# NESCAT.net
KiCad netlist of a schematic drawn in EAGLE
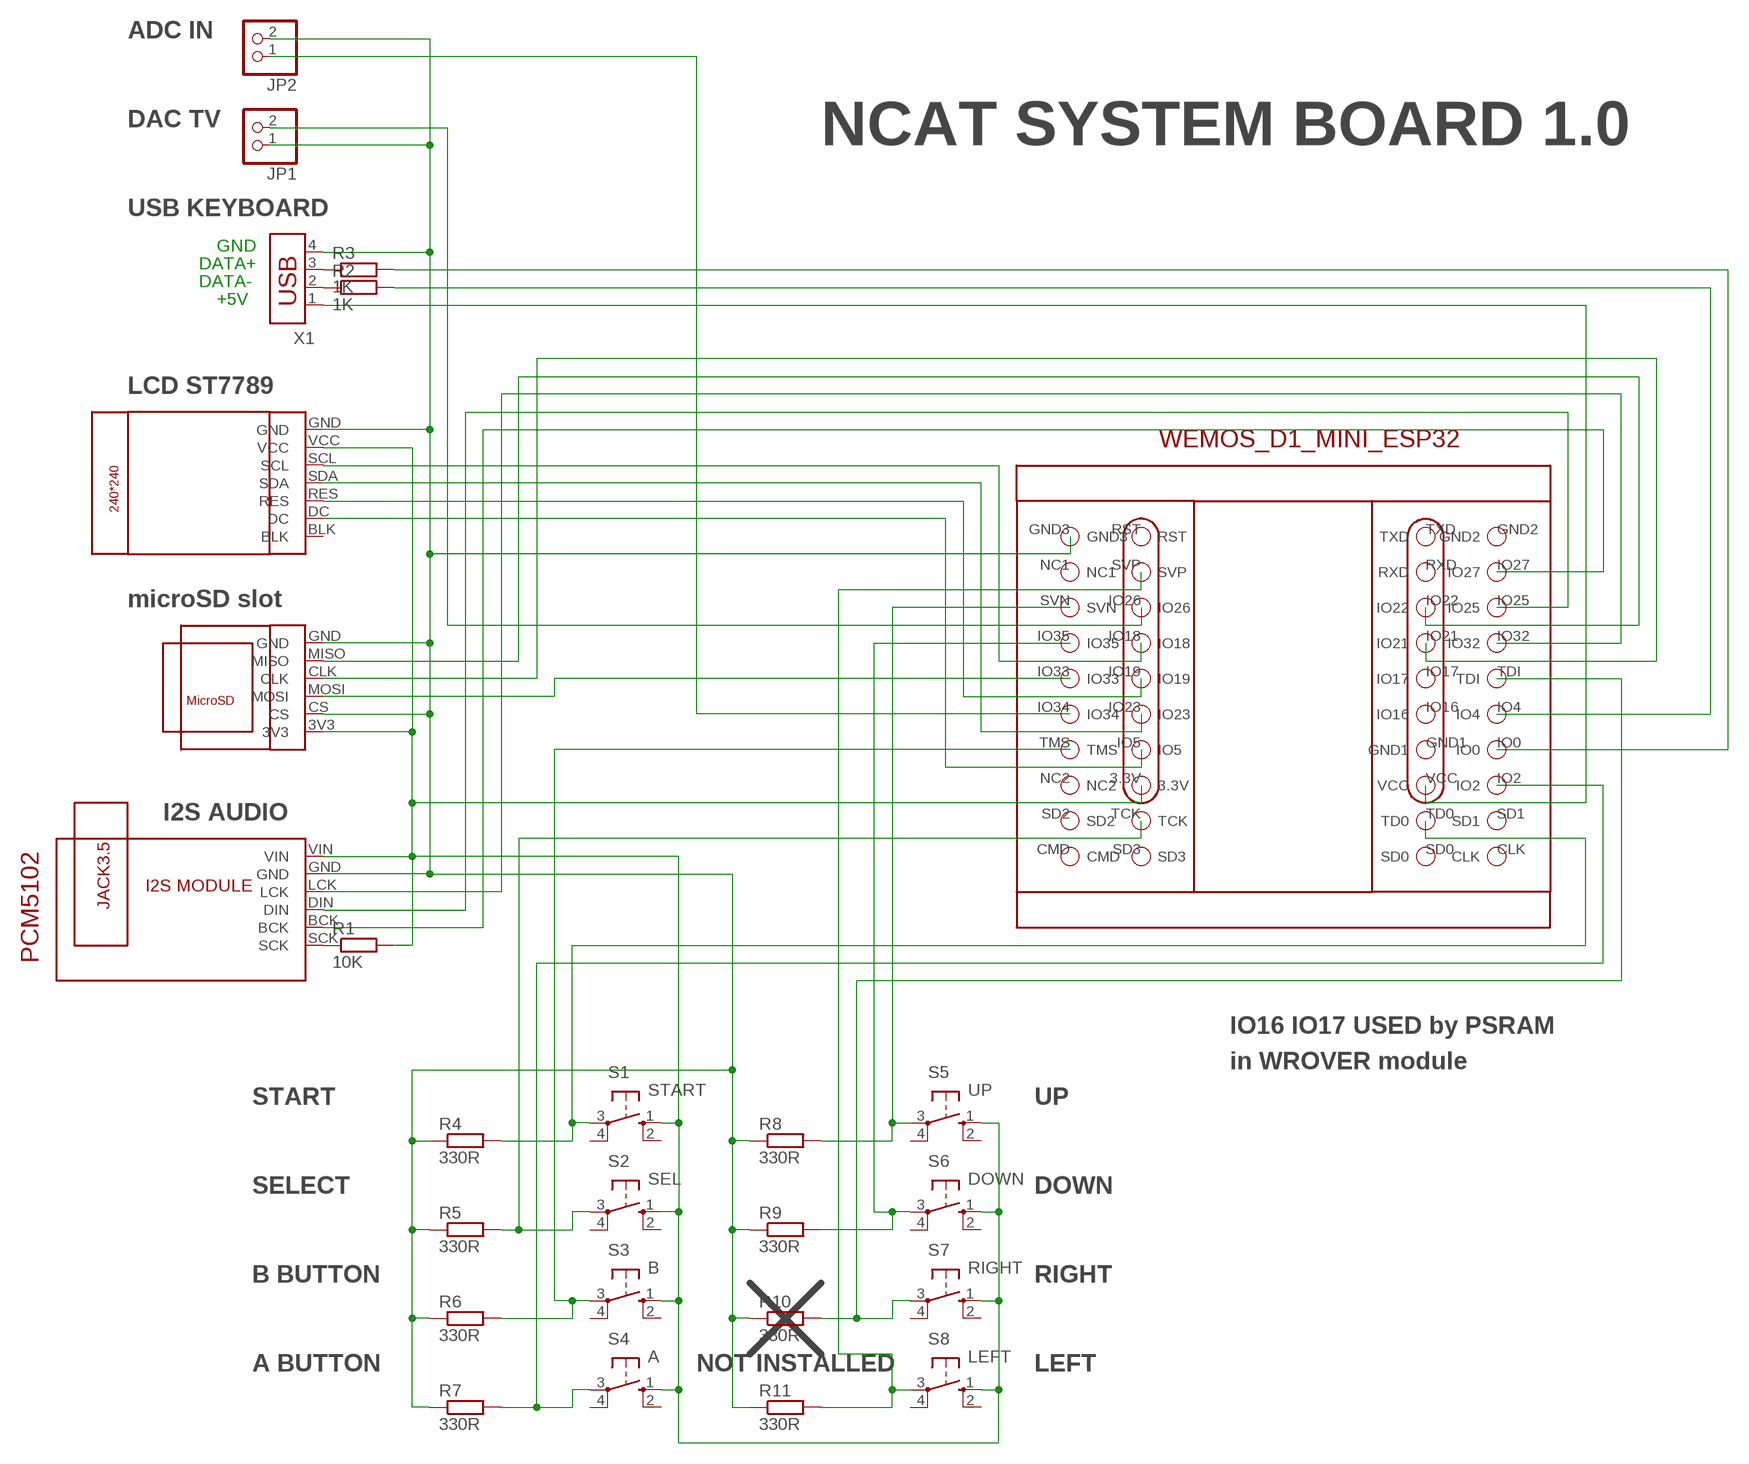
[diagram p0: schematic, sheet 1]

(export (version "E")
  (design (tool "Eeschema 10.0.6"))
  (components
    (comp (ref "JP1")
      (value "PINHD-1X2/90")
      (footprint "eagle-import:1X02_90")
      (libsource (lib "eagle-import") (part "PINHD-1X2/90"))
    )
    (comp (ref "JP2")
      (value "PINHD-1X2/90")
      (footprint "eagle-import:1X02_90")
      (libsource (lib "eagle-import") (part "PINHD-1X2/90"))
    )
    (comp (ref "R1")
      (value "10K")
      (footprint "eagle-import:R-0207_10H")
      (libsource (lib "eagle-import") (part "R-RESISTORR-0207/10H"))
    )
    (comp (ref "R2")
      (value "1K")
      (footprint "eagle-import:R-0207_10H")
      (libsource (lib "eagle-import") (part "R-RESISTORR-0207/10H"))
    )
    (comp (ref "R3")
      (value "1K")
      (footprint "eagle-import:R-0207_10H")
      (libsource (lib "eagle-import") (part "R-RESISTORR-0207/10H"))
    )
    (comp (ref "R4")
      (value "330R")
      (footprint "eagle-import:R-0207_10H")
      (libsource (lib "eagle-import") (part "R-RESISTORR-0207/10H"))
    )
    (comp (ref "R5")
      (value "330R")
      (footprint "eagle-import:R-0207_10H")
      (libsource (lib "eagle-import") (part "R-RESISTORR-0207/10H"))
    )
    (comp (ref "R6")
      (value "330R")
      (footprint "eagle-import:R-0207_10H")
      (libsource (lib "eagle-import") (part "R-RESISTORR-0207/10H"))
    )
    (comp (ref "R7")
      (value "330R")
      (footprint "eagle-import:R-0207_10H")
      (libsource (lib "eagle-import") (part "R-RESISTORR-0207/10H"))
    )
    (comp (ref "R8")
      (value "330R")
      (footprint "eagle-import:R-0207_10H")
      (libsource (lib "eagle-import") (part "R-RESISTORR-0207/10H"))
    )
    (comp (ref "R9")
      (value "330R")
      (footprint "eagle-import:R-0207_10H")
      (libsource (lib "eagle-import") (part "R-RESISTORR-0207/10H"))
    )
    (comp (ref "R10")
      (value "330R")
      (footprint "eagle-import:R-0207_10H")
      (libsource (lib "eagle-import") (part "R-RESISTORR-0207/10H"))
    )
    (comp (ref "R11")
      (value "330R")
      (footprint "eagle-import:R-0207_10H")
      (libsource (lib "eagle-import") (part "R-RESISTORR-0207/10H"))
    )
    (comp (ref "S1")
      (value "START")
      (footprint "eagle-import:B3F-10XX")
      (fields (field (name "MPN") "B3F-1000"))
      (libsource (lib "eagle-import") (part "10-XX"))
    )
    (comp (ref "S2")
      (value "SEL")
      (footprint "eagle-import:B3F-10XX")
      (fields (field (name "MPN") "B3F-1000"))
      (libsource (lib "eagle-import") (part "10-XX"))
    )
    (comp (ref "S3")
      (value "B")
      (footprint "eagle-import:B3F-10XX")
      (fields (field (name "MPN") "B3F-1000"))
      (libsource (lib "eagle-import") (part "10-XX"))
    )
    (comp (ref "S4")
      (value "A")
      (footprint "eagle-import:B3F-10XX")
      (fields (field (name "MPN") "B3F-1000"))
      (libsource (lib "eagle-import") (part "10-XX"))
    )
    (comp (ref "S5")
      (value "UP")
      (footprint "eagle-import:B3F-10XX")
      (fields (field (name "MPN") "B3F-1000"))
      (libsource (lib "eagle-import") (part "10-XX"))
    )
    (comp (ref "S6")
      (value "DOWN")
      (footprint "eagle-import:B3F-10XX")
      (fields (field (name "MPN") "B3F-1000"))
      (libsource (lib "eagle-import") (part "10-XX"))
    )
    (comp (ref "S7")
      (value "RIGHT")
      (footprint "eagle-import:B3F-10XX")
      (fields (field (name "MPN") "B3F-1000"))
      (libsource (lib "eagle-import") (part "10-XX"))
    )
    (comp (ref "S8")
      (value "LEFT")
      (footprint "eagle-import:B3F-10XX")
      (fields (field (name "MPN") "B3F-1000"))
      (libsource (lib "eagle-import") (part "10-XX"))
    )
    (comp (ref "U$1")
      (value "WEMOS_D1_MINI_ESP32")
      (footprint "eagle-import:WEMOS_D1_MINI_ESP32")
      (libsource (lib "eagle-import") (part "WEMOS_D1_MINI_ESP32"))
    )
    (comp (ref "U$2")
      (value "ST7789-1.3INCH")
      (footprint "eagle-import:ST7789-1.3INCH")
      (libsource (lib "eagle-import") (part "ST7789-1.3INCH"))
    )
    (comp (ref "U$3")
      (value "MICROSD-CARD-MODULE")
      (footprint "eagle-import:MICROSD-CARD-MODULE")
      (libsource (lib "eagle-import") (part "MICROSD-CARD-MODULE"))
    )
    (comp (ref "U$4")
      (value "I2S-MODULE-PCM5102A-LITE")
      (footprint "eagle-import:I2S-MODULE-PCM5102A-LITE")
      (libsource (lib "eagle-import") (part "I2S-MODULE-PCM5102A-LITE"))
    )
    (comp (ref "X1")
      (value "USB-787616")
      (footprint "eagle-import:USB")
      (libsource (lib "eagle-import") (part "USB-787616"))
    )
  )
  (nets
    (net (code "1") (name "Net-(JP1-Pad1)") (class "Default")
      (node (ref "JP1") (pin "1") (pinfunction "1_1") (pintype "passive"))
      (node (ref "JP2") (pin "2") (pinfunction "2_2") (pintype "passive"))
      (node (ref "R10") (pin "1") (pinfunction "1_1") (pintype "passive"))
      (node (ref "R11") (pin "1") (pinfunction "1_1") (pintype "passive"))
      (node (ref "R4") (pin "1") (pinfunction "1_1") (pintype "passive"))
      (node (ref "R5") (pin "1") (pinfunction "1_1") (pintype "passive"))
      (node (ref "R6") (pin "1") (pinfunction "1_1") (pintype "passive"))
      (node (ref "R7") (pin "1") (pinfunction "1_1") (pintype "passive"))
      (node (ref "R8") (pin "1") (pinfunction "1_1") (pintype "passive"))
      (node (ref "R9") (pin "1") (pinfunction "1_1") (pintype "passive"))
      (node (ref "U$1") (pin "GND3") (pinfunction "GND3_GND3") (pintype "bidirectional"))
      (node (ref "U$2") (pin "GND") (pinfunction "GND_GND") (pintype "bidirectional"))
      (node (ref "U$3") (pin "CS") (pinfunction "CS_CS") (pintype "bidirectional"))
      (node (ref "U$3") (pin "GND") (pinfunction "GND_GND") (pintype "bidirectional"))
      (node (ref "U$4") (pin "GND") (pinfunction "GND_GND") (pintype "bidirectional"))
      (node (ref "X1") (pin "4") (pinfunction "4_4") (pintype "passive"))
    )
    (net (code "2") (name "Net-(JP1-Pad2)") (class "Default")
      (node (ref "JP1") (pin "2") (pinfunction "2_2") (pintype "passive"))
      (node (ref "U$1") (pin "IO26") (pinfunction "IO26_IO26") (pintype "bidirectional"))
    )
    (net (code "3") (name "Net-(JP2-Pad1)") (class "Default")
      (node (ref "JP2") (pin "1") (pinfunction "1_1") (pintype "passive"))
      (node (ref "U$1") (pin "IO34") (pinfunction "IO34_IO34") (pintype "bidirectional"))
    )
    (net (code "4") (name "Net-(R1-Pad1)") (class "Default")
      (node (ref "R1") (pin "1") (pinfunction "1_1") (pintype "passive"))
      (node (ref "U$4") (pin "SCK") (pinfunction "SCK_SCK") (pintype "bidirectional"))
    )
    (net (code "5") (name "Net-(R2-Pad1)") (class "Default")
      (node (ref "R2") (pin "1") (pinfunction "1_1") (pintype "passive"))
      (node (ref "X1") (pin "2") (pinfunction "2_2") (pintype "passive"))
    )
    (net (code "6") (name "Net-(R2-Pad2)") (class "Default")
      (node (ref "R2") (pin "2") (pinfunction "2_2") (pintype "passive"))
      (node (ref "U$1") (pin "IO4") (pinfunction "IO4_IO4") (pintype "bidirectional"))
    )
    (net (code "7") (name "Net-(R3-Pad1)") (class "Default")
      (node (ref "R3") (pin "1") (pinfunction "1_1") (pintype "passive"))
      (node (ref "X1") (pin "3") (pinfunction "3_3") (pintype "passive"))
    )
    (net (code "8") (name "Net-(R3-Pad2)") (class "Default")
      (node (ref "R3") (pin "2") (pinfunction "2_2") (pintype "passive"))
      (node (ref "U$1") (pin "IO0") (pinfunction "IO0_IO0") (pintype "bidirectional"))
    )
    (net (code "9") (name "Net-(S1-P)") (class "Default")
      (node (ref "R4") (pin "2") (pinfunction "2_2") (pintype "passive"))
      (node (ref "S1") (pin "3") (pinfunction "P_3") (pintype "passive"))
      (node (ref "U$1") (pin "TD0") (pinfunction "TD0_TD0") (pintype "bidirectional"))
    )
    (net (code "10") (name "Net-(S1-S)") (class "Default")
      (node (ref "R1") (pin "2") (pinfunction "2_2") (pintype "passive"))
      (node (ref "S1") (pin "1") (pinfunction "S_1") (pintype "passive"))
      (node (ref "S2") (pin "1") (pinfunction "S_1") (pintype "passive"))
      (node (ref "S3") (pin "1") (pinfunction "S_1") (pintype "passive"))
      (node (ref "S4") (pin "1") (pinfunction "S_1") (pintype "passive"))
      (node (ref "S5") (pin "1") (pinfunction "S_1") (pintype "passive"))
      (node (ref "S6") (pin "1") (pinfunction "S_1") (pintype "passive"))
      (node (ref "S7") (pin "1") (pinfunction "S_1") (pintype "passive"))
      (node (ref "S8") (pin "1") (pinfunction "S_1") (pintype "passive"))
      (node (ref "U$1") (pin "3.3V") (pinfunction "3.3V_3.3V") (pintype "bidirectional"))
      (node (ref "U$2") (pin "VCC") (pinfunction "VCC_VCC") (pintype "bidirectional"))
      (node (ref "U$3") (pin "3V3") (pinfunction "3V3_3V3") (pintype "bidirectional"))
      (node (ref "U$4") (pin "VIN") (pinfunction "VIN_VIN") (pintype "bidirectional"))
    )
    (net (code "11") (name "Net-(S2-P)") (class "Default")
      (node (ref "R5") (pin "2") (pinfunction "2_2") (pintype "passive"))
      (node (ref "S2") (pin "3") (pinfunction "P_3") (pintype "passive"))
      (node (ref "U$1") (pin "TCK") (pinfunction "TCK_TCK") (pintype "bidirectional"))
    )
    (net (code "12") (name "Net-(S3-P)") (class "Default")
      (node (ref "R6") (pin "2") (pinfunction "2_2") (pintype "passive"))
      (node (ref "S3") (pin "3") (pinfunction "P_3") (pintype "passive"))
      (node (ref "U$1") (pin "TMS") (pinfunction "TMS_TMS") (pintype "bidirectional"))
    )
    (net (code "13") (name "Net-(S4-P)") (class "Default")
      (node (ref "R7") (pin "2") (pinfunction "2_2") (pintype "passive"))
      (node (ref "S4") (pin "3") (pinfunction "P_3") (pintype "passive"))
      (node (ref "U$1") (pin "IO2") (pinfunction "IO2_IO2") (pintype "bidirectional"))
    )
    (net (code "14") (name "Net-(S5-P)") (class "Default")
      (node (ref "R8") (pin "2") (pinfunction "2_2") (pintype "passive"))
      (node (ref "S5") (pin "3") (pinfunction "P_3") (pintype "passive"))
      (node (ref "U$1") (pin "SVN") (pinfunction "SVN_SVN") (pintype "bidirectional"))
    )
    (net (code "15") (name "Net-(S6-P)") (class "Default")
      (node (ref "R9") (pin "2") (pinfunction "2_2") (pintype "passive"))
      (node (ref "S6") (pin "3") (pinfunction "P_3") (pintype "passive"))
      (node (ref "U$1") (pin "IO35") (pinfunction "IO35_IO35") (pintype "bidirectional"))
    )
    (net (code "16") (name "Net-(S7-P)") (class "Default")
      (node (ref "R10") (pin "2") (pinfunction "2_2") (pintype "passive"))
      (node (ref "S7") (pin "3") (pinfunction "P_3") (pintype "passive"))
      (node (ref "U$1") (pin "TDI") (pinfunction "TDI_TDI") (pintype "bidirectional"))
    )
    (net (code "17") (name "Net-(S8-P)") (class "Default")
      (node (ref "R11") (pin "2") (pinfunction "2_2") (pintype "passive"))
      (node (ref "S8") (pin "3") (pinfunction "P_3") (pintype "passive"))
      (node (ref "U$1") (pin "SVP") (pinfunction "SVP_SVP") (pintype "bidirectional"))
    )
    (net (code "18") (name "Net-(U$1-PadIO5)") (class "Default")
      (node (ref "U$1") (pin "IO5") (pinfunction "IO5_IO5") (pintype "bidirectional"))
      (node (ref "U$2") (pin "DC") (pinfunction "DC_DC") (pintype "bidirectional"))
    )
    (net (code "19") (name "Net-(U$1-PadIO18)") (class "Default")
      (node (ref "U$1") (pin "IO18") (pinfunction "IO18_IO18") (pintype "bidirectional"))
      (node (ref "U$2") (pin "SCL") (pinfunction "SCL_SCL") (pintype "bidirectional"))
    )
    (net (code "20") (name "Net-(U$1-PadIO19)") (class "Default")
      (node (ref "U$1") (pin "IO19") (pinfunction "IO19_IO19") (pintype "bidirectional"))
      (node (ref "U$2") (pin "RES") (pinfunction "RES_RES") (pintype "bidirectional"))
    )
    (net (code "21") (name "Net-(U$1-PadIO21)") (class "Default")
      (node (ref "U$1") (pin "IO21") (pinfunction "IO21_IO21") (pintype "bidirectional"))
      (node (ref "U$3") (pin "CLK") (pinfunction "CLK_CLK") (pintype "bidirectional"))
    )
    (net (code "22") (name "Net-(U$1-PadIO22)") (class "Default")
      (node (ref "U$1") (pin "IO22") (pinfunction "IO22_IO22") (pintype "bidirectional"))
      (node (ref "U$3") (pin "MISO") (pinfunction "MISO_MISO") (pintype "bidirectional"))
    )
    (net (code "23") (name "Net-(U$1-PadIO23)") (class "Default")
      (node (ref "U$1") (pin "IO23") (pinfunction "IO23_IO23") (pintype "bidirectional"))
      (node (ref "U$2") (pin "SDA") (pinfunction "SDA_SDA") (pintype "bidirectional"))
    )
    (net (code "24") (name "Net-(U$1-PadIO25)") (class "Default")
      (node (ref "U$1") (pin "IO25") (pinfunction "IO25_IO25") (pintype "bidirectional"))
      (node (ref "U$4") (pin "DIN") (pinfunction "DIN_DIN") (pintype "bidirectional"))
    )
    (net (code "25") (name "Net-(U$1-PadIO27)") (class "Default")
      (node (ref "U$1") (pin "IO27") (pinfunction "IO27_IO27") (pintype "bidirectional"))
      (node (ref "U$4") (pin "BCK") (pinfunction "BCK_BCK") (pintype "bidirectional"))
    )
    (net (code "26") (name "Net-(U$1-PadIO32)") (class "Default")
      (node (ref "U$1") (pin "IO32") (pinfunction "IO32_IO32") (pintype "bidirectional"))
      (node (ref "U$4") (pin "LCK") (pinfunction "LCK_LCK") (pintype "bidirectional"))
    )
    (net (code "27") (name "Net-(U$1-PadIO33)") (class "Default")
      (node (ref "U$1") (pin "IO33") (pinfunction "IO33_IO33") (pintype "bidirectional"))
      (node (ref "U$3") (pin "MOSI") (pinfunction "MOSI_MOSI") (pintype "bidirectional"))
    )
    (net (code "28") (name "Net-(U$1-PadVCC)") (class "Default")
      (node (ref "U$1") (pin "VCC") (pinfunction "VCC_VCC") (pintype "bidirectional"))
      (node (ref "X1") (pin "1") (pinfunction "1_1") (pintype "passive"))
    )
    (net (code "29") (name "unconnected-(S1-P1-Pad4)") (class "Default")
      (node (ref "S1") (pin "4") (pinfunction "P1_4") (pintype "passive"))
    )
    (net (code "30") (name "unconnected-(S1-S1-Pad2)") (class "Default")
      (node (ref "S1") (pin "2") (pinfunction "S1_2") (pintype "passive"))
    )
    (net (code "31") (name "unconnected-(S2-P1-Pad4)") (class "Default")
      (node (ref "S2") (pin "4") (pinfunction "P1_4") (pintype "passive"))
    )
    (net (code "32") (name "unconnected-(S2-S1-Pad2)") (class "Default")
      (node (ref "S2") (pin "2") (pinfunction "S1_2") (pintype "passive"))
    )
    (net (code "33") (name "unconnected-(S3-P1-Pad4)") (class "Default")
      (node (ref "S3") (pin "4") (pinfunction "P1_4") (pintype "passive"))
    )
    (net (code "34") (name "unconnected-(S3-S1-Pad2)") (class "Default")
      (node (ref "S3") (pin "2") (pinfunction "S1_2") (pintype "passive"))
    )
    (net (code "35") (name "unconnected-(S4-P1-Pad4)") (class "Default")
      (node (ref "S4") (pin "4") (pinfunction "P1_4") (pintype "passive"))
    )
    (net (code "36") (name "unconnected-(S4-S1-Pad2)") (class "Default")
      (node (ref "S4") (pin "2") (pinfunction "S1_2") (pintype "passive"))
    )
    (net (code "37") (name "unconnected-(S5-P1-Pad4)") (class "Default")
      (node (ref "S5") (pin "4") (pinfunction "P1_4") (pintype "passive"))
    )
    (net (code "38") (name "unconnected-(S5-S1-Pad2)") (class "Default")
      (node (ref "S5") (pin "2") (pinfunction "S1_2") (pintype "passive"))
    )
    (net (code "39") (name "unconnected-(S6-P1-Pad4)") (class "Default")
      (node (ref "S6") (pin "4") (pinfunction "P1_4") (pintype "passive"))
    )
    (net (code "40") (name "unconnected-(S6-S1-Pad2)") (class "Default")
      (node (ref "S6") (pin "2") (pinfunction "S1_2") (pintype "passive"))
    )
    (net (code "41") (name "unconnected-(S7-P1-Pad4)") (class "Default")
      (node (ref "S7") (pin "4") (pinfunction "P1_4") (pintype "passive"))
    )
    (net (code "42") (name "unconnected-(S7-S1-Pad2)") (class "Default")
      (node (ref "S7") (pin "2") (pinfunction "S1_2") (pintype "passive"))
    )
    (net (code "43") (name "unconnected-(S8-P1-Pad4)") (class "Default")
      (node (ref "S8") (pin "4") (pinfunction "P1_4") (pintype "passive"))
    )
    (net (code "44") (name "unconnected-(S8-S1-Pad2)") (class "Default")
      (node (ref "S8") (pin "2") (pinfunction "S1_2") (pintype "passive"))
    )
    (net (code "45") (name "unconnected-(U$1-PadCLK)") (class "Default")
      (node (ref "U$1") (pin "CLK") (pinfunction "CLK_CLK") (pintype "bidirectional"))
    )
    (net (code "46") (name "unconnected-(U$1-PadCMD)") (class "Default")
      (node (ref "U$1") (pin "CMD") (pinfunction "CMD_CMD") (pintype "bidirectional"))
    )
    (net (code "47") (name "unconnected-(U$1-PadGND1)") (class "Default")
      (node (ref "U$1") (pin "GND1") (pinfunction "GND1_GND1") (pintype "bidirectional"))
    )
    (net (code "48") (name "unconnected-(U$1-PadGND2)") (class "Default")
      (node (ref "U$1") (pin "GND2") (pinfunction "GND2_GND2") (pintype "bidirectional"))
    )
    (net (code "49") (name "unconnected-(U$1-PadIO16)") (class "Default")
      (node (ref "U$1") (pin "IO16") (pinfunction "IO16_IO16") (pintype "bidirectional"))
    )
    (net (code "50") (name "unconnected-(U$1-PadIO17)") (class "Default")
      (node (ref "U$1") (pin "IO17") (pinfunction "IO17_IO17") (pintype "bidirectional"))
    )
    (net (code "51") (name "unconnected-(U$1-PadNC1)") (class "Default")
      (node (ref "U$1") (pin "NC1") (pinfunction "NC1_NC1") (pintype "bidirectional"))
    )
    (net (code "52") (name "unconnected-(U$1-PadNC2)") (class "Default")
      (node (ref "U$1") (pin "NC2") (pinfunction "NC2_NC2") (pintype "bidirectional"))
    )
    (net (code "53") (name "unconnected-(U$1-PadRST)") (class "Default")
      (node (ref "U$1") (pin "RST") (pinfunction "RST_RST") (pintype "bidirectional"))
    )
    (net (code "54") (name "unconnected-(U$1-PadRXD)") (class "Default")
      (node (ref "U$1") (pin "RXD") (pinfunction "RXD_RXD") (pintype "bidirectional"))
    )
    (net (code "55") (name "unconnected-(U$1-PadSD0)") (class "Default")
      (node (ref "U$1") (pin "SD0") (pinfunction "SD0_SD0") (pintype "bidirectional"))
    )
    (net (code "56") (name "unconnected-(U$1-PadSD1)") (class "Default")
      (node (ref "U$1") (pin "SD1") (pinfunction "SD1_SD1") (pintype "bidirectional"))
    )
    (net (code "57") (name "unconnected-(U$1-PadSD2)") (class "Default")
      (node (ref "U$1") (pin "SD2") (pinfunction "SD2_SD2") (pintype "bidirectional"))
    )
    (net (code "58") (name "unconnected-(U$1-PadSD3)") (class "Default")
      (node (ref "U$1") (pin "SD3") (pinfunction "SD3_SD3") (pintype "bidirectional"))
    )
    (net (code "59") (name "unconnected-(U$1-PadTXD)") (class "Default")
      (node (ref "U$1") (pin "TXD") (pinfunction "TXD_TXD") (pintype "bidirectional"))
    )
    (net (code "60") (name "unconnected-(U$2-PadBLK)") (class "Default")
      (node (ref "U$2") (pin "BLK") (pinfunction "BLK_BLK") (pintype "bidirectional"))
    )
  )
)
